# CS_NAV.net
KiCad netlist of a schematic drawn in EAGLE
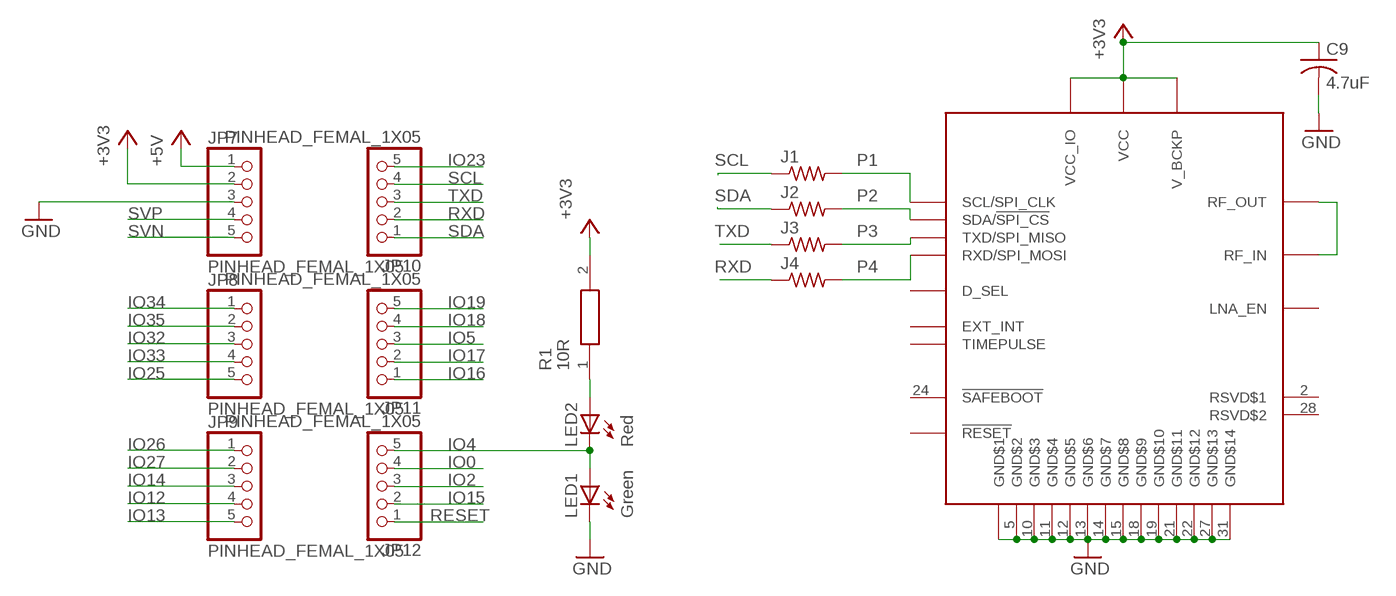
[diagram p0: schematic, sheet 1]

(export (version "E")
  (design (tool "Eeschema 10.0.6"))
  (components
    (comp (ref "C9")
      (value "4.7uF")
      (footprint "eagle-import:C0805")
      (libsource (lib "eagle-import") (part "C-USC0805"))
    )
    (comp (ref "CAM-M8C/Q")
      (value "CAM-M8")
      (footprint "eagle-import:CAM-M8")
      (libsource (lib "eagle-import") (part "CAM-M8"))
    )
    (comp (ref "J1")
      (value "R-US_R1206")
      (footprint "eagle-import:R1206")
      (libsource (lib "eagle-import") (part "R-US_R1206"))
    )
    (comp (ref "J2")
      (value "R-US_R1206")
      (footprint "eagle-import:R1206")
      (libsource (lib "eagle-import") (part "R-US_R1206"))
    )
    (comp (ref "J3")
      (value "R-US_R1206")
      (footprint "eagle-import:R1206")
      (libsource (lib "eagle-import") (part "R-US_R1206"))
    )
    (comp (ref "J4")
      (value "R-US_R1206")
      (footprint "eagle-import:R1206")
      (libsource (lib "eagle-import") (part "R-US_R1206"))
    )
    (comp (ref "JP7")
      (value "PINHEAD_FEMAL_1X05")
      (footprint "eagle-import:1X05F")
      (libsource (lib "eagle-import") (part "PINHEAD_FEMAL_1X05"))
    )
    (comp (ref "JP8")
      (value "PINHEAD_FEMAL_1X05")
      (footprint "eagle-import:1X05F")
      (libsource (lib "eagle-import") (part "PINHEAD_FEMAL_1X05"))
    )
    (comp (ref "JP9")
      (value "PINHEAD_FEMAL_1X05")
      (footprint "eagle-import:1X05F")
      (libsource (lib "eagle-import") (part "PINHEAD_FEMAL_1X05"))
    )
    (comp (ref "JP10")
      (value "PINHEAD_FEMAL_1X05")
      (footprint "eagle-import:1X05F")
      (libsource (lib "eagle-import") (part "PINHEAD_FEMAL_1X05"))
    )
    (comp (ref "JP11")
      (value "PINHEAD_FEMAL_1X05")
      (footprint "eagle-import:1X05F")
      (libsource (lib "eagle-import") (part "PINHEAD_FEMAL_1X05"))
    )
    (comp (ref "JP12")
      (value "PINHEAD_FEMAL_1X05")
      (footprint "eagle-import:1X05F")
      (libsource (lib "eagle-import") (part "PINHEAD_FEMAL_1X05"))
    )
    (comp (ref "LED1")
      (value "Green")
      (footprint "eagle-import:CHIPLED_0805")
      (libsource (lib "eagle-import") (part "LEDCHIPLED_0805"))
    )
    (comp (ref "LED2")
      (value "Red")
      (footprint "eagle-import:CHIPLED_0805")
      (libsource (lib "eagle-import") (part "LEDCHIPLED_0805"))
    )
    (comp (ref "R1")
      (value "10R")
      (footprint "eagle-import:RESC2012X60N")
      (fields
        (field (name "MANUFACTURER_PART_NUMBER") "ERA-6AED684V")
        (field (name "MOUSER_PART_NUMBER") "667-ERA-6AED684V")
      )
      (libsource (lib "eagle-import") (part "ERA-6AED684V"))
    )
  )
  (nets
    (net (code "1") (name "+3V3") (class "Default")
      (node (ref "C9") (pin "1") (pinfunction "1_1") (pintype "passive"))
      (node (ref "CAM-M8C/Q") (pin "1") (pinfunction "VCC_IO_1") (pintype "power_in"))
      (node (ref "CAM-M8C/Q") (pin "8") (pinfunction "V_BCKP_8") (pintype "power_in"))
      (node (ref "CAM-M8C/Q") (pin "9") (pinfunction "VCC_9") (pintype "power_in"))
      (node (ref "JP7") (pin "2") (pinfunction "2_2") (pintype "passive"))
      (node (ref "R1") (pin "2") (pinfunction "2_2") (pintype "bidirectional"))
    )
    (net (code "2") (name "+5V") (class "Default")
      (node (ref "JP7") (pin "1") (pinfunction "1_1") (pintype "passive"))
    )
    (net (code "3") (name "/IO0") (class "Default")
      (node (ref "JP12") (pin "4") (pinfunction "4_4") (pintype "passive"))
    )
    (net (code "4") (name "/IO2") (class "Default")
      (node (ref "JP12") (pin "3") (pinfunction "3_3") (pintype "passive"))
    )
    (net (code "5") (name "/IO4") (class "Default")
      (node (ref "JP12") (pin "5") (pinfunction "5_5") (pintype "passive"))
      (node (ref "LED1") (pin "A") (pinfunction "A_A") (pintype "passive"))
      (node (ref "LED2") (pin "C") (pinfunction "C_C") (pintype "passive"))
    )
    (net (code "6") (name "/IO5") (class "Default")
      (node (ref "JP11") (pin "3") (pinfunction "3_3") (pintype "passive"))
    )
    (net (code "7") (name "/IO12") (class "Default")
      (node (ref "JP9") (pin "4") (pinfunction "4_4") (pintype "passive"))
    )
    (net (code "8") (name "/IO13") (class "Default")
      (node (ref "JP9") (pin "5") (pinfunction "5_5") (pintype "passive"))
    )
    (net (code "9") (name "/IO14") (class "Default")
      (node (ref "JP9") (pin "3") (pinfunction "3_3") (pintype "passive"))
    )
    (net (code "10") (name "/IO15") (class "Default")
      (node (ref "JP12") (pin "2") (pinfunction "2_2") (pintype "passive"))
    )
    (net (code "11") (name "/IO16") (class "Default")
      (node (ref "JP11") (pin "1") (pinfunction "1_1") (pintype "passive"))
    )
    (net (code "12") (name "/IO17") (class "Default")
      (node (ref "JP11") (pin "2") (pinfunction "2_2") (pintype "passive"))
    )
    (net (code "13") (name "/IO18") (class "Default")
      (node (ref "JP11") (pin "4") (pinfunction "4_4") (pintype "passive"))
    )
    (net (code "14") (name "/IO19") (class "Default")
      (node (ref "JP11") (pin "5") (pinfunction "5_5") (pintype "passive"))
    )
    (net (code "15") (name "/IO23") (class "Default")
      (node (ref "JP10") (pin "5") (pinfunction "5_5") (pintype "passive"))
    )
    (net (code "16") (name "/IO25") (class "Default")
      (node (ref "JP8") (pin "5") (pinfunction "5_5") (pintype "passive"))
    )
    (net (code "17") (name "/IO26") (class "Default")
      (node (ref "JP9") (pin "1") (pinfunction "1_1") (pintype "passive"))
    )
    (net (code "18") (name "/IO27") (class "Default")
      (node (ref "JP9") (pin "2") (pinfunction "2_2") (pintype "passive"))
    )
    (net (code "19") (name "/IO32") (class "Default")
      (node (ref "JP8") (pin "3") (pinfunction "3_3") (pintype "passive"))
    )
    (net (code "20") (name "/IO33") (class "Default")
      (node (ref "JP8") (pin "4") (pinfunction "4_4") (pintype "passive"))
    )
    (net (code "21") (name "/IO34") (class "Default")
      (node (ref "JP8") (pin "1") (pinfunction "1_1") (pintype "passive"))
    )
    (net (code "22") (name "/IO35") (class "Default")
      (node (ref "JP8") (pin "2") (pinfunction "2_2") (pintype "passive"))
    )
    (net (code "23") (name "/P1") (class "Default")
      (node (ref "CAM-M8C/Q") (pin "6") (pinfunction "SCL/SPI_CLK_6") (pintype "input"))
      (node (ref "J1") (pin "2") (pinfunction "2_2") (pintype "passive"))
    )
    (net (code "24") (name "/P2") (class "Default")
      (node (ref "CAM-M8C/Q") (pin "3") (pinfunction "SDA/~{SPI_CS}_3") (pintype "bidirectional"))
      (node (ref "J2") (pin "2") (pinfunction "2_2") (pintype "passive"))
    )
    (net (code "25") (name "/P3") (class "Default")
      (node (ref "CAM-M8C/Q") (pin "25") (pinfunction "TXD/SPI_MISO_25") (pintype "output"))
      (node (ref "J3") (pin "2") (pinfunction "2_2") (pintype "passive"))
    )
    (net (code "26") (name "/P4") (class "Default")
      (node (ref "CAM-M8C/Q") (pin "26") (pinfunction "RXD/SPI_MOSI_26") (pintype "input"))
      (node (ref "J4") (pin "2") (pinfunction "2_2") (pintype "passive"))
    )
    (net (code "27") (name "/RESET") (class "Default")
      (node (ref "JP12") (pin "1") (pinfunction "1_1") (pintype "passive"))
    )
    (net (code "28") (name "/RXD") (class "Default")
      (node (ref "J4") (pin "1") (pinfunction "1_1") (pintype "passive"))
      (node (ref "JP10") (pin "2") (pinfunction "2_2") (pintype "passive"))
    )
    (net (code "29") (name "/SCL") (class "Default")
      (node (ref "J1") (pin "1") (pinfunction "1_1") (pintype "passive"))
      (node (ref "JP10") (pin "4") (pinfunction "4_4") (pintype "passive"))
    )
    (net (code "30") (name "/SDA") (class "Default")
      (node (ref "J2") (pin "1") (pinfunction "1_1") (pintype "passive"))
      (node (ref "JP10") (pin "1") (pinfunction "1_1") (pintype "passive"))
    )
    (net (code "31") (name "/SVN") (class "Default")
      (node (ref "JP7") (pin "5") (pinfunction "5_5") (pintype "passive"))
    )
    (net (code "32") (name "/SVP") (class "Default")
      (node (ref "JP7") (pin "4") (pinfunction "4_4") (pintype "passive"))
    )
    (net (code "33") (name "/TXD") (class "Default")
      (node (ref "J3") (pin "1") (pinfunction "1_1") (pintype "passive"))
      (node (ref "JP10") (pin "3") (pinfunction "3_3") (pintype "passive"))
    )
    (net (code "34") (name "GND") (class "Default")
      (node (ref "C9") (pin "2") (pinfunction "2_2") (pintype "passive"))
      (node (ref "CAM-M8C/Q") (pin "10") (pinfunction "GND$3_10") (pintype "power_in"))
      (node (ref "CAM-M8C/Q") (pin "11") (pinfunction "GND$4_11") (pintype "power_in"))
      (node (ref "CAM-M8C/Q") (pin "12") (pinfunction "GND$5_12") (pintype "power_in"))
      (node (ref "CAM-M8C/Q") (pin "13") (pinfunction "GND$6_13") (pintype "power_in"))
      (node (ref "CAM-M8C/Q") (pin "14") (pinfunction "GND$7_14") (pintype "power_in"))
      (node (ref "CAM-M8C/Q") (pin "15") (pinfunction "GND$8_15") (pintype "power_in"))
      (node (ref "CAM-M8C/Q") (pin "18") (pinfunction "GND$9_18") (pintype "power_in"))
      (node (ref "CAM-M8C/Q") (pin "19") (pinfunction "GND$10_19") (pintype "power_in"))
      (node (ref "CAM-M8C/Q") (pin "21") (pinfunction "GND$11_21") (pintype "power_in"))
      (node (ref "CAM-M8C/Q") (pin "22") (pinfunction "GND$12_22") (pintype "power_in"))
      (node (ref "CAM-M8C/Q") (pin "27") (pinfunction "GND$13_27") (pintype "power_in"))
      (node (ref "CAM-M8C/Q") (pin "31") (pinfunction "GND$14_31") (pintype "power_in"))
      (node (ref "CAM-M8C/Q") (pin "4") (pinfunction "GND$1_4") (pintype "power_in"))
      (node (ref "CAM-M8C/Q") (pin "5") (pinfunction "GND$2_5") (pintype "power_in"))
      (node (ref "JP7") (pin "3") (pinfunction "3_3") (pintype "passive"))
      (node (ref "LED1") (pin "C") (pinfunction "C_C") (pintype "passive"))
    )
    (net (code "35") (name "Net-(CAM-M8C/Q-RF_IN)") (class "Default")
      (node (ref "CAM-M8C/Q") (pin "16") (pinfunction "RF_OUT_16") (pintype "output"))
      (node (ref "CAM-M8C/Q") (pin "17") (pinfunction "RF_IN_17") (pintype "input"))
    )
    (net (code "36") (name "Net-(LED2-PadA)") (class "Default")
      (node (ref "LED2") (pin "A") (pinfunction "A_A") (pintype "passive"))
      (node (ref "R1") (pin "1") (pinfunction "1_1") (pintype "bidirectional"))
    )
    (net (code "37") (name "unconnected-(CAM-M8C/Q-D_SEL-Pad20)") (class "Default")
      (node (ref "CAM-M8C/Q") (pin "20") (pinfunction "D_SEL_20") (pintype "input"))
    )
    (net (code "38") (name "unconnected-(CAM-M8C/Q-EXT_INT-Pad7)") (class "Default")
      (node (ref "CAM-M8C/Q") (pin "7") (pinfunction "EXT_INT_7") (pintype "bidirectional"))
    )
    (net (code "39") (name "unconnected-(CAM-M8C/Q-LNA_EN-Pad30)") (class "Default")
      (node (ref "CAM-M8C/Q") (pin "30") (pinfunction "LNA_EN_30") (pintype "output"))
    )
    (net (code "40") (name "unconnected-(CAM-M8C/Q-RSVD$1-Pad2)") (class "Default")
      (node (ref "CAM-M8C/Q") (pin "2") (pinfunction "RSVD$1_2") (pintype "no_connect"))
    )
    (net (code "41") (name "unconnected-(CAM-M8C/Q-RSVD$2-Pad28)") (class "Default")
      (node (ref "CAM-M8C/Q") (pin "28") (pinfunction "RSVD$2_28") (pintype "no_connect"))
    )
    (net (code "42") (name "unconnected-(CAM-M8C/Q-TIMEPULSE-Pad29)") (class "Default")
      (node (ref "CAM-M8C/Q") (pin "29") (pinfunction "TIMEPULSE_29") (pintype "output"))
    )
    (net (code "43") (name "unconnected-(CAM-M8C/Q-~{RESET}-Pad23)") (class "Default")
      (node (ref "CAM-M8C/Q") (pin "23") (pinfunction "~{RESET}_23") (pintype "input"))
    )
    (net (code "44") (name "unconnected-(CAM-M8C/Q-~{SAFEBOOT}-Pad24)") (class "Default")
      (node (ref "CAM-M8C/Q") (pin "24") (pinfunction "~{SAFEBOOT}_24") (pintype "input"))
    )
  )
)
